# V1.net
KiCad netlist of a schematic drawn in Altium Designer
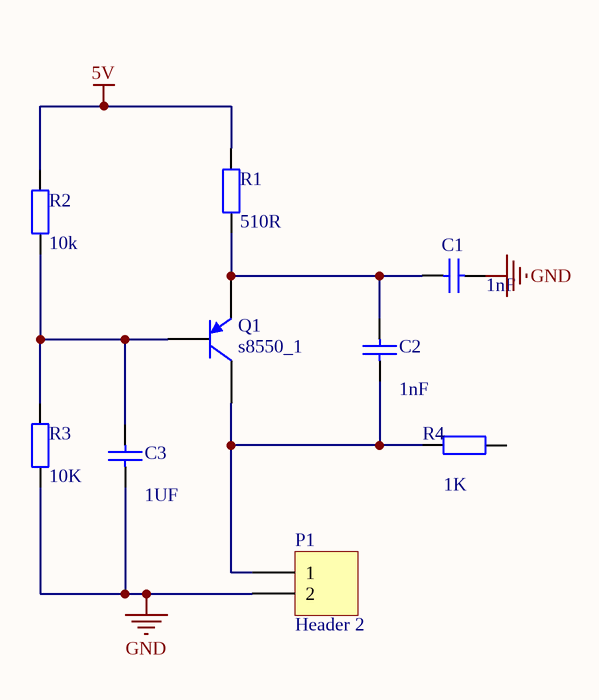
[diagram p0: 官方方案V1.SchDoc]

(export (version "E")
  (design (tool "Eeschema 10.0.6"))
  (components
    (comp (ref "C1")
      (value "1nF")
      (footprint "RAD-0.3")
      (description "Capacitor")
      (fields (field (name "Comment") "Cap") (field (name "PUBLISHER") "Altium Limited"))
      (libsource (lib "Miscellaneous Devices") (part "Cap"))
    )
    (comp (ref "C2")
      (value "1nF")
      (footprint "RAD-0.3")
      (description "Capacitor")
      (fields (field (name "Comment") "Cap") (field (name "PUBLISHER") "Altium Limited"))
      (libsource (lib "Miscellaneous Devices") (part "Cap"))
    )
    (comp (ref "C3")
      (value "1UF")
      (footprint "RAD-0.3")
      (description "Capacitor")
      (fields (field (name "Comment") "Cap") (field (name "PUBLISHER") "Altium Limited"))
      (libsource (lib "Miscellaneous Devices") (part "Cap"))
    )
    (comp (ref "P1")
      (value "Header 2")
      (footprint "HDR1X2")
      (description "Header, 2-Pin")
      (fields (field (name "PUBLISHER") "Altium Limited"))
      (libsource (lib "Miscellaneous Connectors") (part "Header 2"))
    )
    (comp (ref "Q1")
      (value "s8550_1")
      (footprint "TO-92A")
      (description "PNP General Purpose Amplifier")
      (fields (field (name "PUBLISHER") "Altium Limited"))
      (libsource (lib "Miscellaneous Devices") (part "2N3906"))
    )
    (comp (ref "R1")
      (value "510R")
      (footprint "AXIAL-0.4")
      (description "Resistor")
      (fields (field (name "Comment") "Res2") (field (name "PUBLISHER") "Altium Limited"))
      (libsource (lib "Miscellaneous Devices") (part "Res2"))
    )
    (comp (ref "R2")
      (value "10k")
      (footprint "AXIAL-0.4")
      (description "Resistor")
      (fields (field (name "Comment") "Res2") (field (name "PUBLISHER") "Altium Limited"))
      (libsource (lib "Miscellaneous Devices") (part "Res2"))
    )
    (comp (ref "R3")
      (value "10K")
      (footprint "AXIAL-0.4")
      (description "Resistor")
      (fields (field (name "Comment") "Res2") (field (name "PUBLISHER") "Altium Limited"))
      (libsource (lib "Miscellaneous Devices") (part "Res2"))
    )
    (comp (ref "R4")
      (value "1K")
      (footprint "AXIAL-0.4")
      (description "Resistor")
      (fields (field (name "Comment") "Res2") (field (name "PUBLISHER") "Altium Limited"))
      (libsource (lib "") (part "Res2_1"))
    )
  )
  (nets
    (net (code "1") (name "5V") (class "Default")
      (node (ref "R1") (pin "2") (pinfunction "2_2") (pintype "passive"))
      (node (ref "R2") (pin "2") (pinfunction "2_2") (pintype "passive"))
    )
    (net (code "2") (name "GND") (class "Default")
      (node (ref "C1") (pin "2") (pinfunction "2_2") (pintype "passive"))
      (node (ref "C3") (pin "1") (pinfunction "1_1") (pintype "passive"))
      (node (ref "P1") (pin "2") (pinfunction "2_2") (pintype "passive"))
      (node (ref "R3") (pin "1") (pinfunction "1_1") (pintype "passive"))
    )
    (net (code "3") (name "Net-(Q1-B)") (class "Default")
      (node (ref "C3") (pin "2") (pinfunction "2_2") (pintype "passive"))
      (node (ref "Q1") (pin "2") (pinfunction "B_2") (pintype "passive"))
      (node (ref "R2") (pin "1") (pinfunction "1_1") (pintype "passive"))
      (node (ref "R3") (pin "2") (pinfunction "2_2") (pintype "passive"))
    )
    (net (code "4") (name "Net-(Q1-C)") (class "Default")
      (node (ref "C2") (pin "1") (pinfunction "1_1") (pintype "passive"))
      (node (ref "P1") (pin "1") (pinfunction "1_1") (pintype "passive"))
      (node (ref "Q1") (pin "3") (pinfunction "C_3") (pintype "passive"))
      (node (ref "R4") (pin "2") (pinfunction "2_2") (pintype "passive"))
    )
    (net (code "5") (name "Net-(Q1-E)") (class "Default")
      (node (ref "C1") (pin "1") (pinfunction "1_1") (pintype "passive"))
      (node (ref "C2") (pin "2") (pinfunction "2_2") (pintype "passive"))
      (node (ref "Q1") (pin "1") (pinfunction "E_1") (pintype "passive"))
      (node (ref "R1") (pin "1") (pinfunction "1_1") (pintype "passive"))
    )
    (net (code "6") (name "unconnected-(R4-Pad1)") (class "Default")
      (node (ref "R4") (pin "1") (pinfunction "1_1") (pintype "passive"))
    )
  )
)
